# P_Shift.net
KiCad netlist of a schematic drawn in Altium Designer
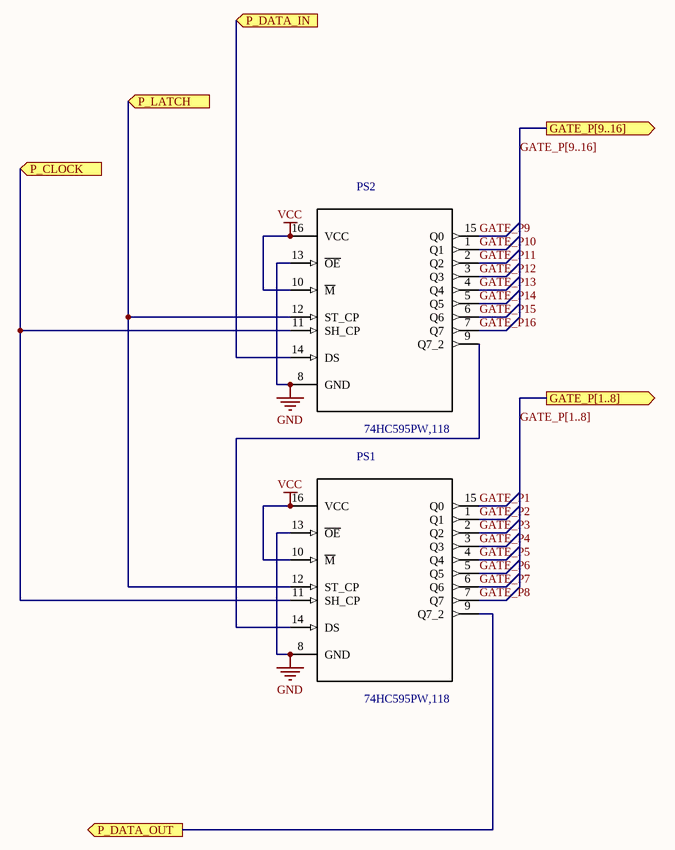
[diagram p0: P_Shift.SchDoc]

(export (version "E")
  (design (tool "Eeschema 10.0.6"))
  (components
    (comp (ref "PS1")
      (value "74HC595PW,118")
      (footprint "SOP65P640X110-16N")
      (description "8-bit serial-in%2C serial or parallel-out shift register with output latches%3B 3-state")
      (fields (field (name "MF") "NXP Semiconductors"))
      (libsource (lib "74HC595PW_118") (part "74HC595PW,118"))
    )
    (comp (ref "PS2")
      (value "74HC595PW,118")
      (footprint "SOP65P640X110-16N")
      (description "8-bit serial-in%2C serial or parallel-out shift register with output latches%3B 3-state")
      (fields (field (name "MF") "NXP Semiconductors"))
      (libsource (lib "74HC595PW_118") (part "74HC595PW,118"))
    )
  )
  (nets
    (net (code "1") (name "/GATE_P1") (class "Default")
      (node (ref "PS1") (pin "15") (pinfunction "Q0_15") (pintype "output"))
    )
    (net (code "2") (name "/GATE_P2") (class "Default")
      (node (ref "PS1") (pin "1") (pinfunction "Q1_1") (pintype "output"))
    )
    (net (code "3") (name "/GATE_P3") (class "Default")
      (node (ref "PS1") (pin "2") (pinfunction "Q2_2") (pintype "output"))
    )
    (net (code "4") (name "/GATE_P4") (class "Default")
      (node (ref "PS1") (pin "3") (pinfunction "Q3_3") (pintype "output"))
    )
    (net (code "5") (name "/GATE_P5") (class "Default")
      (node (ref "PS1") (pin "4") (pinfunction "Q4_4") (pintype "output"))
    )
    (net (code "6") (name "/GATE_P6") (class "Default")
      (node (ref "PS1") (pin "5") (pinfunction "Q5_5") (pintype "output"))
    )
    (net (code "7") (name "/GATE_P7") (class "Default")
      (node (ref "PS1") (pin "6") (pinfunction "Q6_6") (pintype "output"))
    )
    (net (code "8") (name "/GATE_P8") (class "Default")
      (node (ref "PS1") (pin "7") (pinfunction "Q7_7") (pintype "output"))
    )
    (net (code "9") (name "/GATE_P9") (class "Default")
      (node (ref "PS2") (pin "15") (pinfunction "Q0_15") (pintype "output"))
    )
    (net (code "10") (name "/GATE_P10") (class "Default")
      (node (ref "PS2") (pin "1") (pinfunction "Q1_1") (pintype "output"))
    )
    (net (code "11") (name "/GATE_P11") (class "Default")
      (node (ref "PS2") (pin "2") (pinfunction "Q2_2") (pintype "output"))
    )
    (net (code "12") (name "/GATE_P12") (class "Default")
      (node (ref "PS2") (pin "3") (pinfunction "Q3_3") (pintype "output"))
    )
    (net (code "13") (name "/GATE_P13") (class "Default")
      (node (ref "PS2") (pin "4") (pinfunction "Q4_4") (pintype "output"))
    )
    (net (code "14") (name "/GATE_P14") (class "Default")
      (node (ref "PS2") (pin "5") (pinfunction "Q5_5") (pintype "output"))
    )
    (net (code "15") (name "/GATE_P15") (class "Default")
      (node (ref "PS2") (pin "6") (pinfunction "Q6_6") (pintype "output"))
    )
    (net (code "16") (name "/GATE_P16") (class "Default")
      (node (ref "PS2") (pin "7") (pinfunction "Q7_7") (pintype "output"))
    )
    (net (code "19") (name "/P_CLOCK") (class "Default")
      (node (ref "PS1") (pin "11") (pinfunction "SH_CP_11") (pintype "input"))
      (node (ref "PS2") (pin "11") (pinfunction "SH_CP_11") (pintype "input"))
    )
    (net (code "20") (name "/P_DATA_IN") (class "Default")
      (node (ref "PS2") (pin "14") (pinfunction "DS_14") (pintype "input"))
    )
    (net (code "21") (name "/P_DATA_OUT") (class "Default")
      (node (ref "PS1") (pin "9") (pinfunction "Q7_2_9") (pintype "output"))
    )
    (net (code "22") (name "/P_LATCH") (class "Default")
      (node (ref "PS1") (pin "12") (pinfunction "ST_CP_12") (pintype "input"))
      (node (ref "PS2") (pin "12") (pinfunction "ST_CP_12") (pintype "input"))
    )
    (net (code "23") (name "GND") (class "Default")
      (node (ref "PS1") (pin "13") (pinfunction "~{OE}_13") (pintype "input"))
      (node (ref "PS1") (pin "8") (pinfunction "GND_8") (pintype "passive"))
      (node (ref "PS2") (pin "13") (pinfunction "~{OE}_13") (pintype "input"))
      (node (ref "PS2") (pin "8") (pinfunction "GND_8") (pintype "passive"))
    )
    (net (code "24") (name "Net-(PS1-DS)") (class "Default")
      (node (ref "PS1") (pin "14") (pinfunction "DS_14") (pintype "input"))
      (node (ref "PS2") (pin "9") (pinfunction "Q7_2_9") (pintype "output"))
    )
    (net (code "25") (name "VCC") (class "Default")
      (node (ref "PS1") (pin "10") (pinfunction "M~{\r}_10") (pintype "input"))
      (node (ref "PS1") (pin "16") (pinfunction "VCC_16") (pintype "power_in"))
      (node (ref "PS2") (pin "10") (pinfunction "M~{\r}_10") (pintype "input"))
      (node (ref "PS2") (pin "16") (pinfunction "VCC_16") (pintype "power_in"))
    )
  )
)
